# dcv_moduler_incomplete.net
KiCad netlist of a schematic drawn in EAGLE
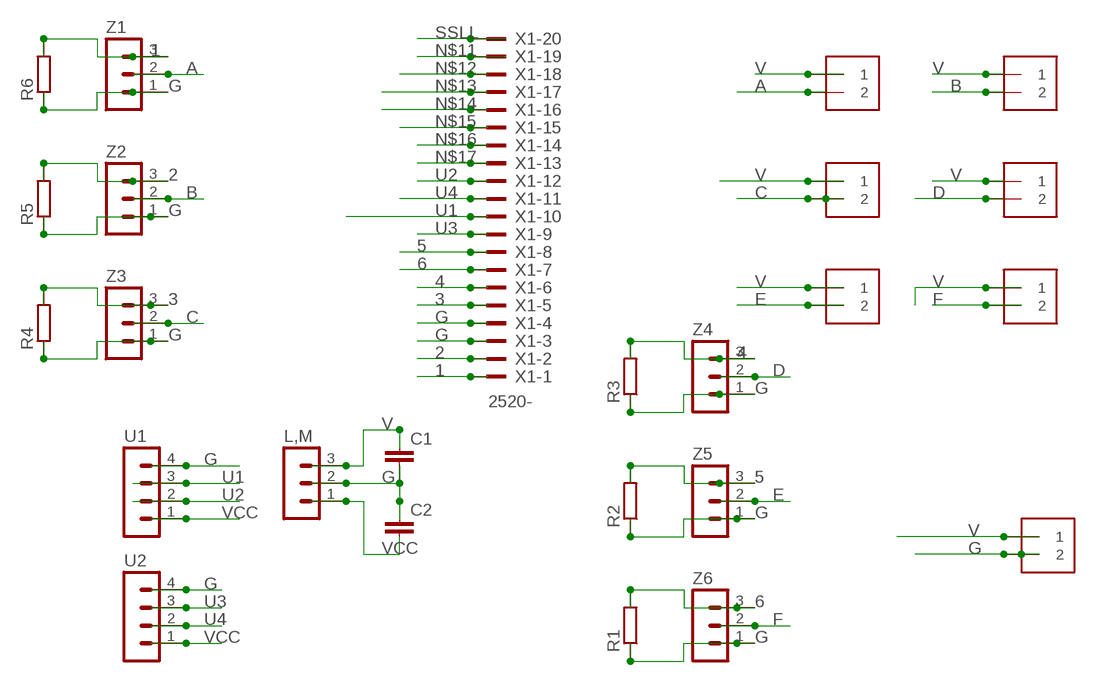
[diagram p0: schematic, sheet 1]

(export (version "E")
  (design (tool "Eeschema 10.0.6"))
  (components
    (comp (ref "C1")
      (value "C2,5-3")
      (footprint "eagle-import:C2.5-3")
      (libsource (lib "eagle-import") (part "C2,5-3"))
    )
    (comp (ref "C2")
      (value "C2,5-3")
      (footprint "eagle-import:C2.5-3")
      (libsource (lib "eagle-import") (part "C2,5-3"))
    )
    (comp (ref "J1")
      (value "1X2-3.5MM")
      (footprint "eagle-import:1X2-3.5MM")
      (libsource (lib "eagle-import") (part "1X2-3.5MM"))
    )
    (comp (ref "J2")
      (value "1X2-3.5MM")
      (footprint "eagle-import:1X2-3.5MM")
      (libsource (lib "eagle-import") (part "1X2-3.5MM"))
    )
    (comp (ref "J3")
      (value "1X2-3.5MM")
      (footprint "eagle-import:1X2-3.5MM")
      (libsource (lib "eagle-import") (part "1X2-3.5MM"))
    )
    (comp (ref "J4")
      (value "1X2-3.5MM")
      (footprint "eagle-import:1X2-3.5MM")
      (libsource (lib "eagle-import") (part "1X2-3.5MM"))
    )
    (comp (ref "J5")
      (value "1X2-3.5MM")
      (footprint "eagle-import:1X2-3.5MM")
      (libsource (lib "eagle-import") (part "1X2-3.5MM"))
    )
    (comp (ref "J6")
      (value "1X2-3.5MM")
      (footprint "eagle-import:1X2-3.5MM")
      (libsource (lib "eagle-import") (part "1X2-3.5MM"))
    )
    (comp (ref "J7")
      (value "1X2-3.5MM")
      (footprint "eagle-import:1X2-3.5MM")
      (libsource (lib "eagle-import") (part "1X2-3.5MM"))
    )
    (comp (ref "L,M")
      (value "MA03-1")
      (footprint "eagle-import:MA03-1")
      (libsource (lib "eagle-import") (part "MA03-1"))
    )
    (comp (ref "R1")
      (value "R-EU_0204_5")
      (footprint "eagle-import:0204_5")
      (libsource (lib "eagle-import") (part "R-EU_0204_5"))
    )
    (comp (ref "R2")
      (value "R-EU_0204_5")
      (footprint "eagle-import:0204_5")
      (libsource (lib "eagle-import") (part "R-EU_0204_5"))
    )
    (comp (ref "R3")
      (value "R-EU_0204_5")
      (footprint "eagle-import:0204_5")
      (libsource (lib "eagle-import") (part "R-EU_0204_5"))
    )
    (comp (ref "R4")
      (value "R-EU_0204_5")
      (footprint "eagle-import:0204_5")
      (libsource (lib "eagle-import") (part "R-EU_0204_5"))
    )
    (comp (ref "R5")
      (value "R-EU_0204_5")
      (footprint "eagle-import:0204_5")
      (libsource (lib "eagle-import") (part "R-EU_0204_5"))
    )
    (comp (ref "R6")
      (value "R-EU_0204_5")
      (footprint "eagle-import:0204_5")
      (libsource (lib "eagle-import") (part "R-EU_0204_5"))
    )
    (comp (ref "U1")
      (value "MA04-1")
      (footprint "eagle-import:MA04-1")
      (libsource (lib "eagle-import") (part "MA04-1"))
    )
    (comp (ref "U2")
      (value "MA04-1")
      (footprint "eagle-import:MA04-1")
      (libsource (lib "eagle-import") (part "MA04-1"))
    )
    (comp (ref "X1")
      (value "2520-")
      (footprint "eagle-import:PAK100_2500-20")
      (libsource (lib "eagle-import") (part "2520-"))
    )
    (comp (ref "Z1")
      (value "MA03-1")
      (footprint "eagle-import:MA03-1")
      (libsource (lib "eagle-import") (part "MA03-1"))
    )
    (comp (ref "Z2")
      (value "MA03-1")
      (footprint "eagle-import:MA03-1")
      (libsource (lib "eagle-import") (part "MA03-1"))
    )
    (comp (ref "Z3")
      (value "MA03-1")
      (footprint "eagle-import:MA03-1")
      (libsource (lib "eagle-import") (part "MA03-1"))
    )
    (comp (ref "Z4")
      (value "MA03-1")
      (footprint "eagle-import:MA03-1")
      (libsource (lib "eagle-import") (part "MA03-1"))
    )
    (comp (ref "Z5")
      (value "MA03-1")
      (footprint "eagle-import:MA03-1")
      (libsource (lib "eagle-import") (part "MA03-1"))
    )
    (comp (ref "Z6")
      (value "MA03-1")
      (footprint "eagle-import:MA03-1")
      (libsource (lib "eagle-import") (part "MA03-1"))
    )
  )
  (nets
    (net (code "1") (name "/1") (class "Default")
      (node (ref "R6") (pin "2") (pinfunction "2_2") (pintype "passive"))
      (node (ref "X1") (pin "1") (pinfunction "KL_1") (pintype "passive"))
      (node (ref "Z1") (pin "3") (pinfunction "3_3") (pintype "passive"))
    )
    (net (code "2") (name "/2") (class "Default")
      (node (ref "R5") (pin "2") (pinfunction "2_2") (pintype "passive"))
      (node (ref "X1") (pin "2") (pinfunction "KL_2") (pintype "passive"))
      (node (ref "Z2") (pin "3") (pinfunction "3_3") (pintype "passive"))
    )
    (net (code "3") (name "/3") (class "Default")
      (node (ref "R4") (pin "2") (pinfunction "2_2") (pintype "passive"))
      (node (ref "X1") (pin "5") (pinfunction "KL_5") (pintype "passive"))
      (node (ref "Z3") (pin "3") (pinfunction "3_3") (pintype "passive"))
    )
    (net (code "4") (name "/4") (class "Default")
      (node (ref "R3") (pin "2") (pinfunction "2_2") (pintype "passive"))
      (node (ref "X1") (pin "6") (pinfunction "KL_6") (pintype "passive"))
      (node (ref "Z4") (pin "3") (pinfunction "3_3") (pintype "passive"))
    )
    (net (code "5") (name "/5") (class "Default")
      (node (ref "R2") (pin "2") (pinfunction "2_2") (pintype "passive"))
      (node (ref "X1") (pin "8") (pinfunction "KL_8") (pintype "passive"))
      (node (ref "Z5") (pin "3") (pinfunction "3_3") (pintype "passive"))
    )
    (net (code "6") (name "/6") (class "Default")
      (node (ref "R1") (pin "2") (pinfunction "2_2") (pintype "passive"))
      (node (ref "X1") (pin "7") (pinfunction "KL_7") (pintype "passive"))
      (node (ref "Z6") (pin "3") (pinfunction "3_3") (pintype "passive"))
    )
    (net (code "7") (name "/A") (class "Default")
      (node (ref "J1") (pin "2") (pinfunction "2_2") (pintype "passive"))
      (node (ref "Z1") (pin "2") (pinfunction "2_2") (pintype "passive"))
    )
    (net (code "8") (name "/B") (class "Default")
      (node (ref "J2") (pin "2") (pinfunction "2_2") (pintype "passive"))
      (node (ref "Z2") (pin "2") (pinfunction "2_2") (pintype "passive"))
    )
    (net (code "9") (name "/C") (class "Default")
      (node (ref "J3") (pin "2") (pinfunction "2_2") (pintype "passive"))
      (node (ref "Z3") (pin "2") (pinfunction "2_2") (pintype "passive"))
    )
    (net (code "10") (name "/D") (class "Default")
      (node (ref "J4") (pin "2") (pinfunction "2_2") (pintype "passive"))
      (node (ref "Z4") (pin "2") (pinfunction "2_2") (pintype "passive"))
    )
    (net (code "11") (name "/E") (class "Default")
      (node (ref "J5") (pin "2") (pinfunction "2_2") (pintype "passive"))
      (node (ref "Z5") (pin "2") (pinfunction "2_2") (pintype "passive"))
    )
    (net (code "12") (name "/F") (class "Default")
      (node (ref "J6") (pin "2") (pinfunction "2_2") (pintype "passive"))
      (node (ref "Z6") (pin "2") (pinfunction "2_2") (pintype "passive"))
    )
    (net (code "13") (name "/G") (class "Default")
      (node (ref "C1") (pin "2") (pinfunction "2_2") (pintype "passive"))
      (node (ref "C2") (pin "1") (pinfunction "1_1") (pintype "passive"))
      (node (ref "J7") (pin "2") (pinfunction "2_2") (pintype "passive"))
      (node (ref "L,M") (pin "2") (pinfunction "2_2") (pintype "passive"))
      (node (ref "R1") (pin "1") (pinfunction "1_1") (pintype "passive"))
      (node (ref "R2") (pin "1") (pinfunction "1_1") (pintype "passive"))
      (node (ref "R3") (pin "1") (pinfunction "1_1") (pintype "passive"))
      (node (ref "R4") (pin "1") (pinfunction "1_1") (pintype "passive"))
      (node (ref "R5") (pin "1") (pinfunction "1_1") (pintype "passive"))
      (node (ref "R6") (pin "1") (pinfunction "1_1") (pintype "passive"))
      (node (ref "U1") (pin "4") (pinfunction "4_4") (pintype "passive"))
      (node (ref "U2") (pin "4") (pinfunction "4_4") (pintype "passive"))
      (node (ref "X1") (pin "3") (pinfunction "KL_3") (pintype "passive"))
      (node (ref "X1") (pin "4") (pinfunction "KL_4") (pintype "passive"))
      (node (ref "Z1") (pin "1") (pinfunction "1_1") (pintype "passive"))
      (node (ref "Z2") (pin "1") (pinfunction "1_1") (pintype "passive"))
      (node (ref "Z3") (pin "1") (pinfunction "1_1") (pintype "passive"))
      (node (ref "Z4") (pin "1") (pinfunction "1_1") (pintype "passive"))
      (node (ref "Z5") (pin "1") (pinfunction "1_1") (pintype "passive"))
      (node (ref "Z6") (pin "1") (pinfunction "1_1") (pintype "passive"))
    )
    (net (code "14") (name "/N$11") (class "Default")
      (node (ref "X1") (pin "19") (pinfunction "KL_19") (pintype "passive"))
    )
    (net (code "15") (name "/N$12") (class "Default")
      (node (ref "X1") (pin "18") (pinfunction "KL_18") (pintype "passive"))
    )
    (net (code "16") (name "/N$13") (class "Default")
      (node (ref "X1") (pin "17") (pinfunction "KL_17") (pintype "passive"))
    )
    (net (code "17") (name "/N$14") (class "Default")
      (node (ref "X1") (pin "16") (pinfunction "KL_16") (pintype "passive"))
    )
    (net (code "18") (name "/N$15") (class "Default")
      (node (ref "X1") (pin "15") (pinfunction "KL_15") (pintype "passive"))
    )
    (net (code "19") (name "/N$16") (class "Default")
      (node (ref "X1") (pin "14") (pinfunction "KL_14") (pintype "passive"))
    )
    (net (code "20") (name "/N$17") (class "Default")
      (node (ref "X1") (pin "13") (pinfunction "KL_13") (pintype "passive"))
    )
    (net (code "21") (name "/SSLL") (class "Default")
      (node (ref "X1") (pin "20") (pinfunction "KL_20") (pintype "passive"))
    )
    (net (code "22") (name "/U1") (class "Default")
      (node (ref "U1") (pin "3") (pinfunction "3_3") (pintype "passive"))
      (node (ref "X1") (pin "10") (pinfunction "KL_10") (pintype "passive"))
    )
    (net (code "23") (name "/U2") (class "Default")
      (node (ref "U1") (pin "2") (pinfunction "2_2") (pintype "passive"))
      (node (ref "X1") (pin "12") (pinfunction "KL_12") (pintype "passive"))
    )
    (net (code "24") (name "/U3") (class "Default")
      (node (ref "U2") (pin "3") (pinfunction "3_3") (pintype "passive"))
      (node (ref "X1") (pin "9") (pinfunction "KL_9") (pintype "passive"))
    )
    (net (code "25") (name "/U4") (class "Default")
      (node (ref "U2") (pin "2") (pinfunction "2_2") (pintype "passive"))
      (node (ref "X1") (pin "11") (pinfunction "KL_11") (pintype "passive"))
    )
    (net (code "26") (name "/V") (class "Default")
      (node (ref "C1") (pin "1") (pinfunction "1_1") (pintype "passive"))
      (node (ref "J1") (pin "1") (pinfunction "1_1") (pintype "passive"))
      (node (ref "J2") (pin "1") (pinfunction "1_1") (pintype "passive"))
      (node (ref "J3") (pin "1") (pinfunction "1_1") (pintype "passive"))
      (node (ref "J4") (pin "1") (pinfunction "1_1") (pintype "passive"))
      (node (ref "J5") (pin "1") (pinfunction "1_1") (pintype "passive"))
      (node (ref "J6") (pin "1") (pinfunction "1_1") (pintype "passive"))
      (node (ref "J7") (pin "1") (pinfunction "1_1") (pintype "passive"))
      (node (ref "L,M") (pin "3") (pinfunction "3_3") (pintype "passive"))
    )
    (net (code "27") (name "/VCC") (class "Default")
      (node (ref "C2") (pin "2") (pinfunction "2_2") (pintype "passive"))
      (node (ref "L,M") (pin "1") (pinfunction "1_1") (pintype "passive"))
      (node (ref "U1") (pin "1") (pinfunction "1_1") (pintype "passive"))
      (node (ref "U2") (pin "1") (pinfunction "1_1") (pintype "passive"))
    )
  )
)
